# 03_-_CONNECTORS.net
KiCad netlist of a schematic drawn in Altium Designer
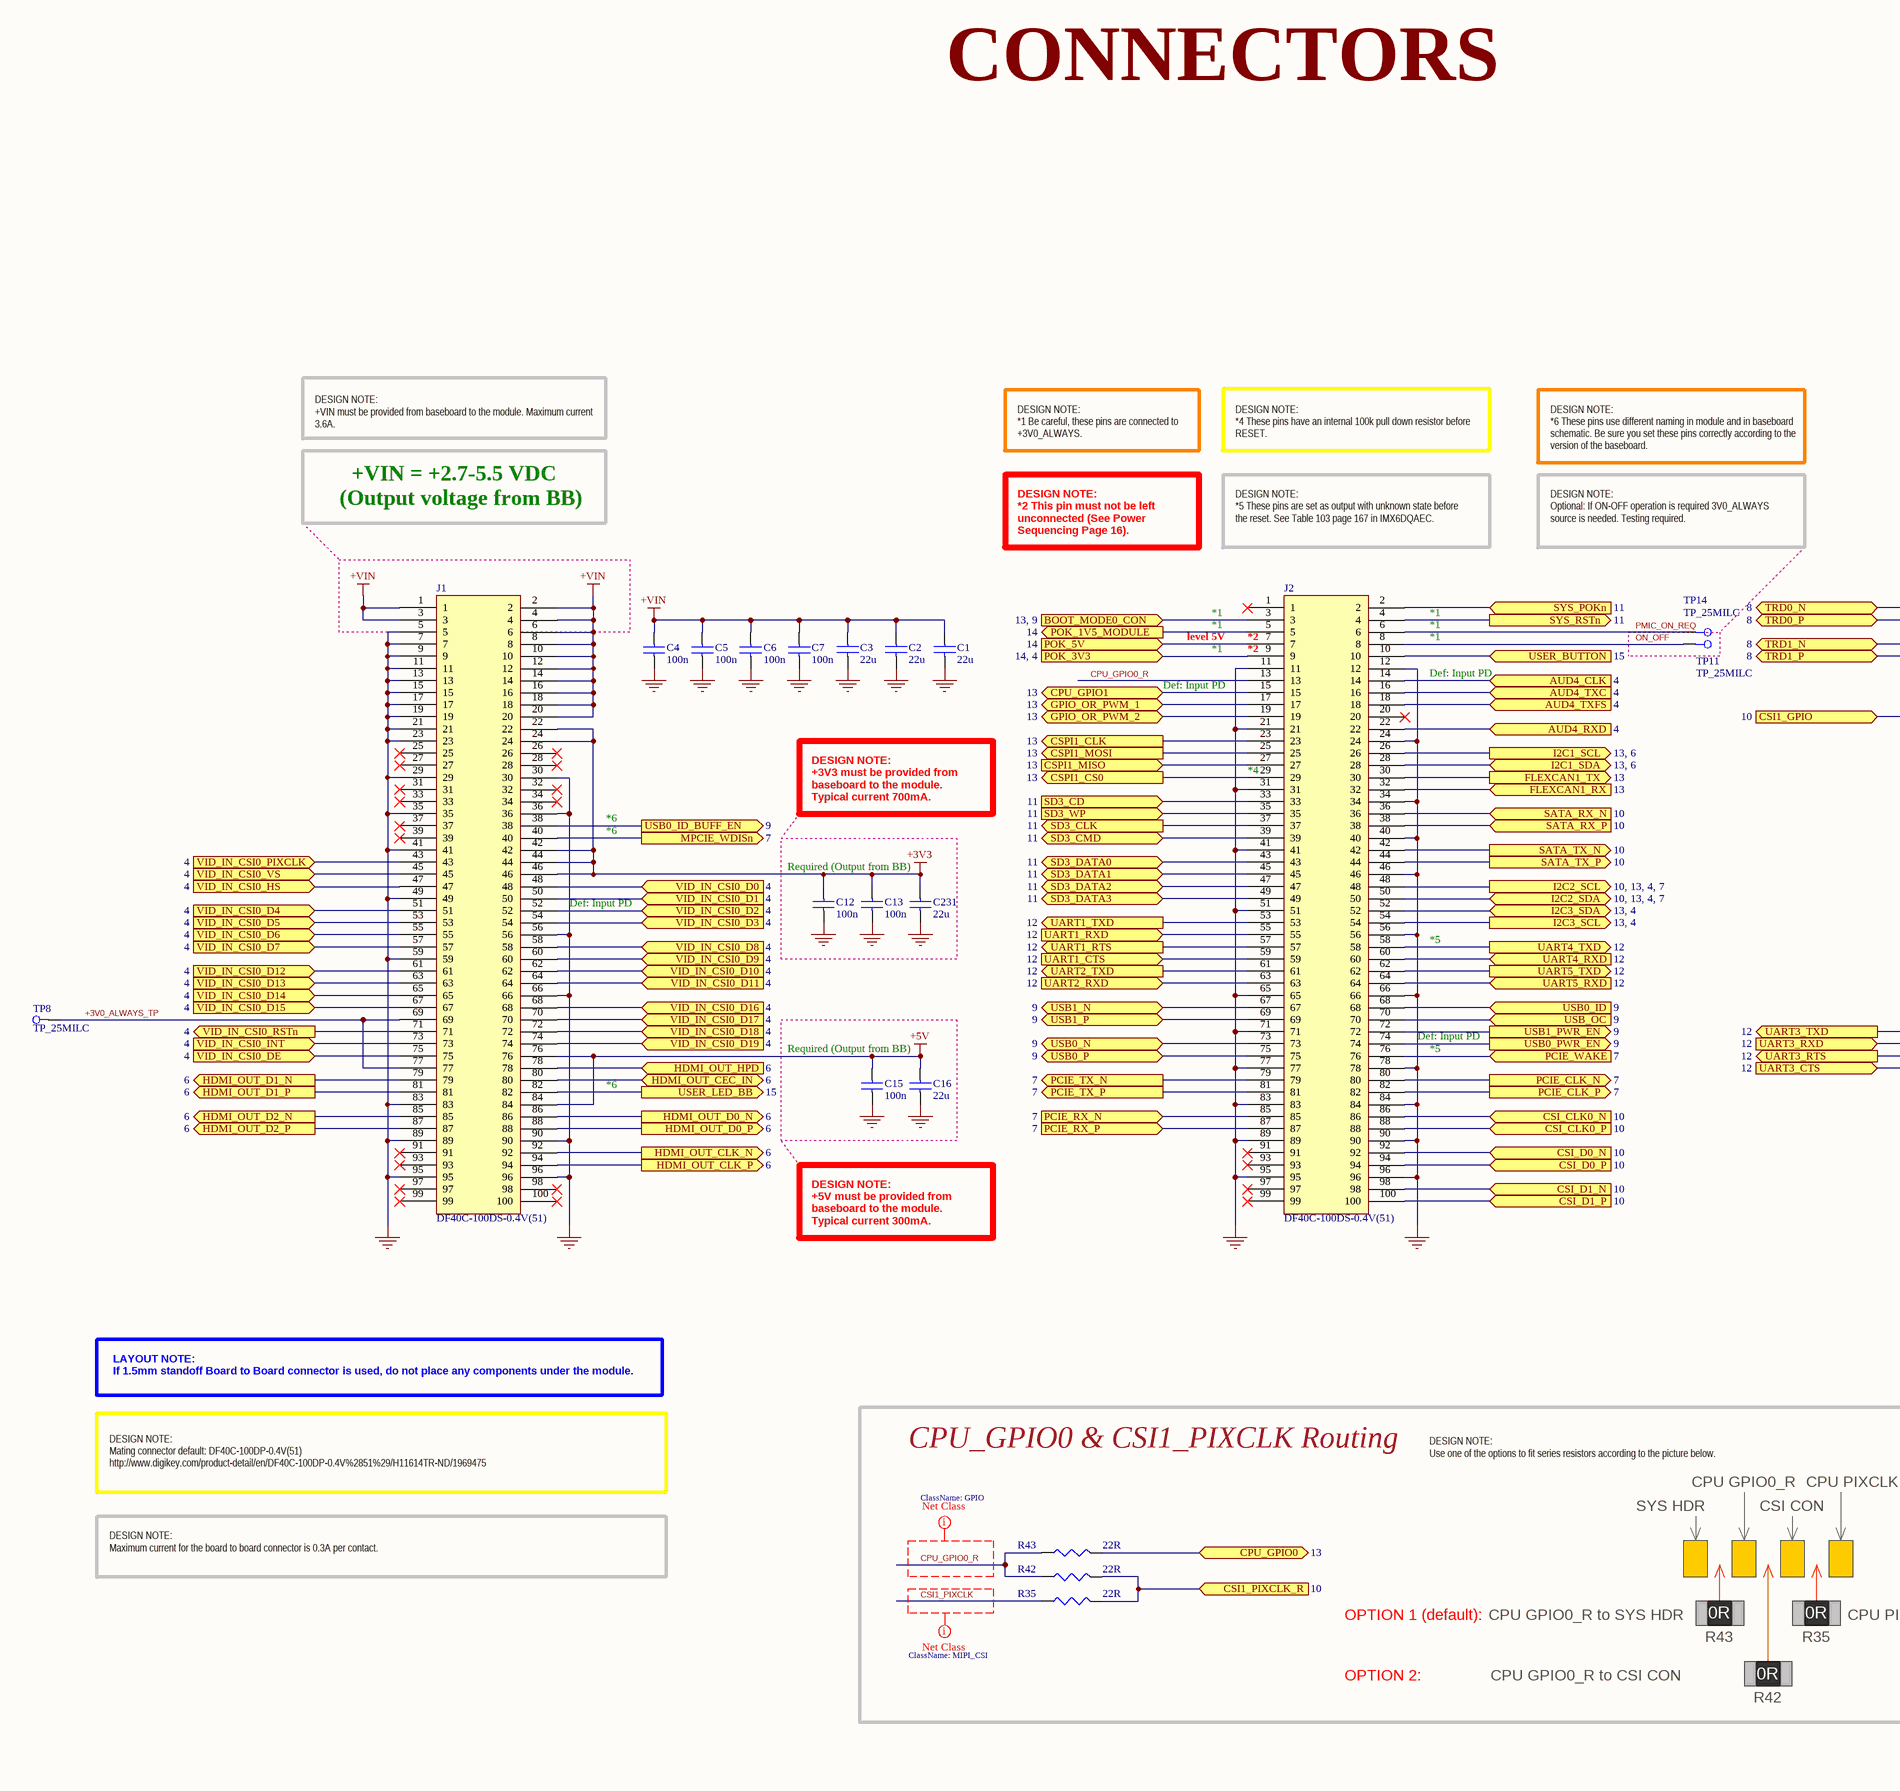
[diagram p0: [03] - CONNECTORS.SchDoc, left]
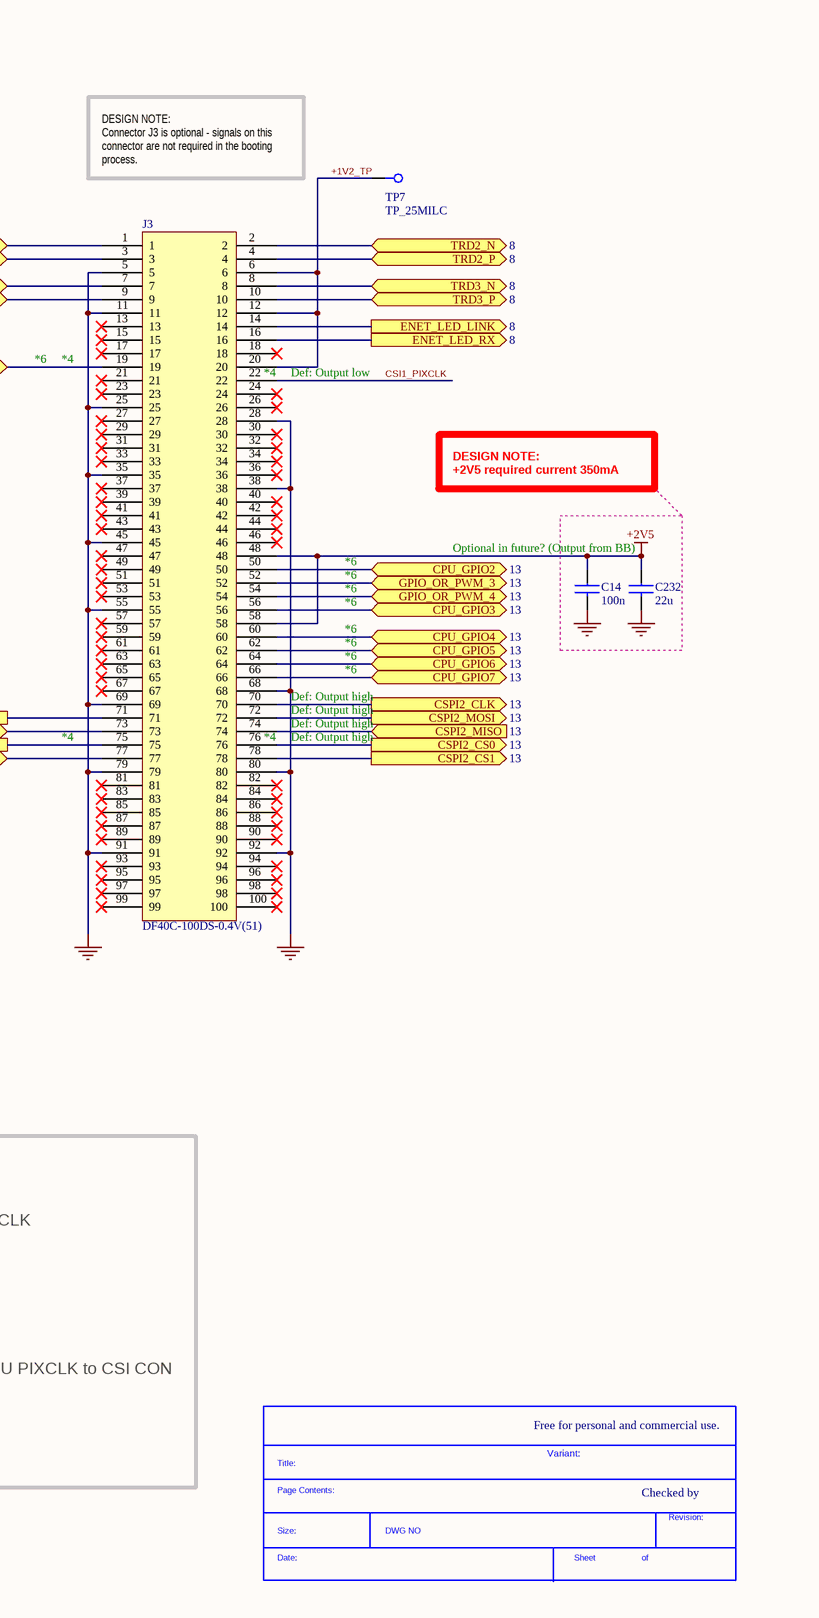
[diagram p1: [03] - CONNECTORS.SchDoc, right]

(export (version "E")
  (design (tool "Eeschema 10.0.6"))
  (components
    (comp (ref "C1")
      (value "22u")
      (footprint "C0603")
      (description "CAP CER 22UF 6.3V 20% X5R 0603")
      (fields
        (field (name "MANUFACTURER") "TDK Corporation")
        (field (name "MANUFACTURER PART NUMBER") "C1608X5R0J226M080AC")
        (field (name ".CREATOR") "MM")
        (field (name ".CHECKED PCB") "MM")
        (field (name ".CHECKED SCH") "MM")
      )
      (libsource (lib "Integrated_Library_FEDEVEL_APR_2015") (part "C1608X5R0J226M080AC"))
    )
    (comp (ref "C2")
      (value "22u")
      (footprint "C0603")
      (description "CAP CER 22UF 6.3V 20% X5R 0603")
      (fields
        (field (name "MANUFACTURER") "TDK Corporation")
        (field (name "MANUFACTURER PART NUMBER") "C1608X5R0J226M080AC")
        (field (name ".CREATOR") "MM")
        (field (name ".CHECKED PCB") "MM")
        (field (name ".CHECKED SCH") "MM")
      )
      (libsource (lib "Integrated_Library_FEDEVEL_APR_2015") (part "C1608X5R0J226M080AC"))
    )
    (comp (ref "C3")
      (value "22u")
      (footprint "C0603")
      (description "CAP CER 22UF 6.3V 20% X5R 0603")
      (fields
        (field (name "MANUFACTURER") "TDK Corporation")
        (field (name "MANUFACTURER PART NUMBER") "C1608X5R0J226M080AC")
        (field (name ".CREATOR") "MM")
        (field (name ".CHECKED PCB") "MM")
        (field (name ".CHECKED SCH") "MM")
      )
      (libsource (lib "Integrated_Library_FEDEVEL_APR_2015") (part "C1608X5R0J226M080AC"))
    )
    (comp (ref "C4")
      (value "100n")
      (footprint "C0402")
      (description "CAP CER .10UF 50V X5R 10% 0402")
      (fields
        (field (name "MANUFACTURER") "TDK Corporation")
        (field (name "MANUFACTURER PART NUMBER") "C1005X5R1H104K")
      )
      (libsource (lib "Integrated_Library_FEDEVEL_APR_2015") (part "C1005X5R1H104K"))
    )
    (comp (ref "C5")
      (value "100n")
      (footprint "C0402")
      (description "CAP CER .10UF 50V X5R 10% 0402")
      (fields
        (field (name "MANUFACTURER") "TDK Corporation")
        (field (name "MANUFACTURER PART NUMBER") "C1005X5R1H104K")
      )
      (libsource (lib "Integrated_Library_FEDEVEL_APR_2015") (part "C1005X5R1H104K"))
    )
    (comp (ref "C6")
      (value "100n")
      (footprint "C0402")
      (description "CAP CER .10UF 50V X5R 10% 0402")
      (fields
        (field (name "MANUFACTURER") "TDK Corporation")
        (field (name "MANUFACTURER PART NUMBER") "C1005X5R1H104K")
      )
      (libsource (lib "Integrated_Library_FEDEVEL_APR_2015") (part "C1005X5R1H104K"))
    )
    (comp (ref "C7")
      (value "100n")
      (footprint "C0402")
      (description "CAP CER .10UF 50V X5R 10% 0402")
      (fields
        (field (name "MANUFACTURER") "TDK Corporation")
        (field (name "MANUFACTURER PART NUMBER") "C1005X5R1H104K")
      )
      (libsource (lib "Integrated_Library_FEDEVEL_APR_2015") (part "C1005X5R1H104K"))
    )
    (comp (ref "C12")
      (value "100n")
      (footprint "C0402")
      (description "CAP CER .10UF 50V X5R 10% 0402")
      (fields
        (field (name "MANUFACTURER") "TDK Corporation")
        (field (name "MANUFACTURER PART NUMBER") "C1005X5R1H104K")
      )
      (libsource (lib "Integrated_Library_FEDEVEL_APR_2015") (part "C1005X5R1H104K"))
    )
    (comp (ref "C13")
      (value "100n")
      (footprint "C0402")
      (description "CAP CER .10UF 50V X5R 10% 0402")
      (fields
        (field (name "MANUFACTURER") "TDK Corporation")
        (field (name "MANUFACTURER PART NUMBER") "C1005X5R1H104K")
      )
      (libsource (lib "Integrated_Library_FEDEVEL_APR_2015") (part "C1005X5R1H104K"))
    )
    (comp (ref "C14")
      (value "100n")
      (footprint "C0402")
      (description "CAP CER .10UF 50V X5R 10% 0402")
      (fields
        (field (name "MANUFACTURER") "TDK Corporation")
        (field (name "MANUFACTURER PART NUMBER") "C1005X5R1H104K")
      )
      (libsource (lib "Integrated_Library_FEDEVEL_APR_2015") (part "C1005X5R1H104K"))
    )
    (comp (ref "C15")
      (value "100n")
      (footprint "C0402")
      (description "CAP CER .10UF 50V X5R 10% 0402")
      (fields
        (field (name "MANUFACTURER") "TDK Corporation")
        (field (name "MANUFACTURER PART NUMBER") "C1005X5R1H104K")
      )
      (libsource (lib "Integrated_Library_FEDEVEL_APR_2015") (part "C1005X5R1H104K"))
    )
    (comp (ref "C16")
      (value "22u")
      (footprint "C0603")
      (description "CAP CER 22UF 6.3V 20% X5R 0603")
      (fields
        (field (name "MANUFACTURER") "TDK Corporation")
        (field (name "MANUFACTURER PART NUMBER") "C1608X5R0J226M080AC")
        (field (name ".CREATOR") "MM")
        (field (name ".CHECKED PCB") "MM")
        (field (name ".CHECKED SCH") "MM")
      )
      (libsource (lib "Integrated_Library_FEDEVEL_APR_2015") (part "C1608X5R0J226M080AC"))
    )
    (comp (ref "C231")
      (value "22u")
      (footprint "C0603")
      (description "CAP CER 22UF 6.3V 20% X5R 0603")
      (fields
        (field (name "MANUFACTURER") "TDK Corporation")
        (field (name "MANUFACTURER PART NUMBER") "C1608X5R0J226M080AC")
        (field (name ".CREATOR") "MM")
        (field (name ".CHECKED PCB") "MM")
        (field (name ".CHECKED SCH") "MM")
      )
      (libsource (lib "Integrated_Library_FEDEVEL_APR_2015") (part "C1608X5R0J226M080AC"))
    )
    (comp (ref "C232")
      (value "22u")
      (footprint "C0603")
      (description "CAP CER 22UF 6.3V 20% X5R 0603")
      (fields
        (field (name "MANUFACTURER") "TDK Corporation")
        (field (name "MANUFACTURER PART NUMBER") "C1608X5R0J226M080AC")
        (field (name ".CREATOR") "MM")
        (field (name ".CHECKED PCB") "MM")
        (field (name ".CHECKED SCH") "MM")
      )
      (libsource (lib "Integrated_Library_FEDEVEL_APR_2015") (part "C1608X5R0J226M080AC"))
    )
    (comp (ref "J1")
      (value "DF40C-100DS-0.4V(51)")
      (footprint "DF40C-100DS-0.4V(51)_V1.1")
      (description "CONN RCPT 100POS 0.4MM SMD GOLD")
      (fields
        (field (name "MANUFACTURER") "Hirose Electric Co Ltd")
        (field (name ".CREATOR") "MM")
        (field (name ".CHECKED PCB") "MM")
        (field (name ".CHECKED SCH") "MM")
      )
      (libsource (lib "Integrated_Library_FEDEVEL_APR_2015") (part "DF40C-100DS-0.4V(51)_v1.1"))
    )
    (comp (ref "J2")
      (value "DF40C-100DS-0.4V(51)")
      (footprint "DF40C-100DS-0.4V(51)_V1.1")
      (description "CONN RCPT 100POS 0.4MM SMD GOLD")
      (fields
        (field (name "MANUFACTURER") "Hirose Electric Co Ltd")
        (field (name ".CREATOR") "MM")
        (field (name ".CHECKED PCB") "MM")
        (field (name ".CHECKED SCH") "MM")
      )
      (libsource (lib "Integrated_Library_FEDEVEL_APR_2015") (part "DF40C-100DS-0.4V(51)_v1.1"))
    )
    (comp (ref "J3")
      (value "DF40C-100DS-0.4V(51)")
      (footprint "DF40C-100DS-0.4V(51)_V1.1")
      (description "CONN RCPT 100POS 0.4MM SMD GOLD")
      (fields
        (field (name "MANUFACTURER") "Hirose Electric Co Ltd")
        (field (name ".CREATOR") "MM")
        (field (name ".CHECKED PCB") "MM")
        (field (name ".CHECKED SCH") "MM")
      )
      (libsource (lib "Integrated_Library_FEDEVEL_APR_2015") (part "DF40C-100DS-0.4V(51)_v1.1"))
    )
    (comp (ref "R35")
      (value "22R")
      (footprint "R0402")
      (description "RES 22.0 OHM 1/16W 1% 0402 SMD")
      (fields
        (field (name "MANUFACTURER") "Yageo")
        (field (name "MANUFACTURER PART NUMBER") "RC0402FR-0722RL")
      )
      (libsource (lib "Integrated_Library_FEDEVEL_APR_2015") (part "RC0402FR-0722RL"))
    )
    (comp (ref "R42")
      (value "22R")
      (footprint "R0402")
      (description "RES 22.0 OHM 1/16W 1% 0402 SMD")
      (fields
        (field (name "MANUFACTURER") "Yageo")
        (field (name "MANUFACTURER PART NUMBER") "RC0402FR-0722RL")
      )
      (libsource (lib "Integrated_Library_FEDEVEL_APR_2015") (part "RC0402FR-0722RL"))
    )
    (comp (ref "R43")
      (value "22R")
      (footprint "R0402")
      (description "RES 22.0 OHM 1/16W 1% 0402 SMD")
      (fields
        (field (name "MANUFACTURER") "Yageo")
        (field (name "MANUFACTURER PART NUMBER") "RC0402FR-0722RL")
      )
      (libsource (lib "Integrated_Library_FEDEVEL_APR_2015") (part "RC0402FR-0722RL"))
    )
    (comp (ref "TP7")
      (value "TP_25MILC")
      (footprint "TP_25C")
      (description "Test Point 25mil")
      (libsource (lib "Integrated_Library_FEDEVEL_APR_2015") (part "TP_25MILC"))
    )
    (comp (ref "TP8")
      (value "TP_25MILC")
      (footprint "TP_25C")
      (description "Test Point 25mil")
      (libsource (lib "Integrated_Library_FEDEVEL_APR_2015") (part "TP_25MILC"))
    )
    (comp (ref "TP11")
      (value "TP_25MILC")
      (footprint "TP_25C")
      (description "Test Point 25mil")
      (libsource (lib "Integrated_Library_FEDEVEL_APR_2015") (part "TP_25MILC"))
    )
    (comp (ref "TP14")
      (value "TP_25MILC")
      (footprint "TP_25C")
      (description "Test Point 25mil")
      (libsource (lib "Integrated_Library_FEDEVEL_APR_2015") (part "TP_25MILC"))
    )
  )
  (nets
    (net (code "1") (name "+2V5") (class "Default")
      (node (ref "C14") (pin "1") (pinfunction "1_1") (pintype "passive"))
      (node (ref "C232") (pin "1") (pinfunction "1_1") (pintype "passive"))
      (node (ref "J3") (pin "48") (pinfunction "48_48") (pintype "passive"))
      (node (ref "J3") (pin "58") (pinfunction "58_58") (pintype "passive"))
    )
    (net (code "2") (name "+3V3") (class "Default")
      (node (ref "C12") (pin "1") (pinfunction "1_1") (pintype "passive"))
      (node (ref "C13") (pin "1") (pinfunction "1_1") (pintype "passive"))
      (node (ref "C231") (pin "1") (pinfunction "1_1") (pintype "passive"))
      (node (ref "J1") (pin "22") (pinfunction "22_22") (pintype "passive"))
      (node (ref "J1") (pin "24") (pinfunction "24_24") (pintype "passive"))
      (node (ref "J1") (pin "42") (pinfunction "42_42") (pintype "passive"))
      (node (ref "J1") (pin "44") (pinfunction "44_44") (pintype "passive"))
      (node (ref "J1") (pin "46") (pinfunction "46_46") (pintype "passive"))
    )
    (net (code "3") (name "+5V") (class "Default")
      (node (ref "C15") (pin "1") (pinfunction "1_1") (pintype "passive"))
      (node (ref "C16") (pin "1") (pinfunction "1_1") (pintype "passive"))
      (node (ref "J1") (pin "76") (pinfunction "76_76") (pintype "passive"))
      (node (ref "J1") (pin "84") (pinfunction "84_84") (pintype "passive"))
    )
    (net (code "4") (name "+VIN") (class "Default")
      (node (ref "C1") (pin "1") (pinfunction "1_1") (pintype "passive"))
      (node (ref "C2") (pin "1") (pinfunction "1_1") (pintype "passive"))
      (node (ref "C3") (pin "1") (pinfunction "1_1") (pintype "passive"))
      (node (ref "C4") (pin "1") (pinfunction "1_1") (pintype "passive"))
      (node (ref "C5") (pin "1") (pinfunction "1_1") (pintype "passive"))
      (node (ref "C6") (pin "1") (pinfunction "1_1") (pintype "passive"))
      (node (ref "C7") (pin "1") (pinfunction "1_1") (pintype "passive"))
      (node (ref "J1") (pin "1") (pinfunction "1_1") (pintype "passive"))
      (node (ref "J1") (pin "10") (pinfunction "10_10") (pintype "passive"))
      (node (ref "J1") (pin "12") (pinfunction "12_12") (pintype "passive"))
      (node (ref "J1") (pin "14") (pinfunction "14_14") (pintype "passive"))
      (node (ref "J1") (pin "16") (pinfunction "16_16") (pintype "passive"))
      (node (ref "J1") (pin "18") (pinfunction "18_18") (pintype "passive"))
      (node (ref "J1") (pin "2") (pinfunction "2_2") (pintype "passive"))
      (node (ref "J1") (pin "20") (pinfunction "20_20") (pintype "passive"))
      (node (ref "J1") (pin "3") (pinfunction "3_3") (pintype "passive"))
      (node (ref "J1") (pin "4") (pinfunction "4_4") (pintype "passive"))
      (node (ref "J1") (pin "6") (pinfunction "6_6") (pintype "passive"))
      (node (ref "J1") (pin "8") (pinfunction "8_8") (pintype "passive"))
    )
    (net (code "5") (name "/+1V2_TP") (class "Default")
      (node (ref "J3") (pin "12") (pinfunction "12_12") (pintype "passive"))
      (node (ref "J3") (pin "20") (pinfunction "20_20") (pintype "passive"))
      (node (ref "J3") (pin "6") (pinfunction "6_6") (pintype "passive"))
      (node (ref "TP7") (pin "1") (pinfunction "1_1") (pintype "passive"))
    )
    (net (code "6") (name "/+3V0_ALWAYS_TP") (class "Default")
      (node (ref "J1") (pin "69") (pinfunction "69_69") (pintype "passive"))
      (node (ref "J1") (pin "77") (pinfunction "77_77") (pintype "passive"))
      (node (ref "TP8") (pin "1") (pinfunction "1_1") (pintype "passive"))
    )
    (net (code "7") (name "/AUD4_CLK") (class "Default")
      (node (ref "J2") (pin "14") (pinfunction "14_14") (pintype "passive"))
    )
    (net (code "8") (name "/AUD4_RXD") (class "Default")
      (node (ref "J2") (pin "22") (pinfunction "22_22") (pintype "passive"))
    )
    (net (code "9") (name "/AUD4_TXC") (class "Default")
      (node (ref "J2") (pin "16") (pinfunction "16_16") (pintype "passive"))
    )
    (net (code "10") (name "/AUD4_TXFS") (class "Default")
      (node (ref "J2") (pin "18") (pinfunction "18_18") (pintype "passive"))
    )
    (net (code "11") (name "/BOOT_MODE0_CON") (class "Default")
      (node (ref "J2") (pin "3") (pinfunction "3_3") (pintype "passive"))
    )
    (net (code "12") (name "/CPU_GPIO0") (class "Default")
      (node (ref "R43") (pin "2") (pinfunction "2_2") (pintype "passive"))
    )
    (net (code "13") (name "/CPU_GPIO0_R") (class "Default")
      (node (ref "J2") (pin "13") (pinfunction "13_13") (pintype "passive"))
      (node (ref "R42") (pin "1") (pinfunction "1_1") (pintype "passive"))
      (node (ref "R43") (pin "1") (pinfunction "1_1") (pintype "passive"))
    )
    (net (code "14") (name "/CPU_GPIO1") (class "Default")
      (node (ref "J2") (pin "15") (pinfunction "15_15") (pintype "passive"))
    )
    (net (code "15") (name "/CPU_GPIO2") (class "Default")
      (node (ref "J3") (pin "50") (pinfunction "50_50") (pintype "passive"))
    )
    (net (code "16") (name "/CPU_GPIO3") (class "Default")
      (node (ref "J3") (pin "56") (pinfunction "56_56") (pintype "passive"))
    )
    (net (code "17") (name "/CPU_GPIO4") (class "Default")
      (node (ref "J3") (pin "60") (pinfunction "60_60") (pintype "passive"))
    )
    (net (code "18") (name "/CPU_GPIO5") (class "Default")
      (node (ref "J3") (pin "62") (pinfunction "62_62") (pintype "passive"))
    )
    (net (code "19") (name "/CPU_GPIO6") (class "Default")
      (node (ref "J3") (pin "64") (pinfunction "64_64") (pintype "passive"))
    )
    (net (code "20") (name "/CPU_GPIO7") (class "Default")
      (node (ref "J3") (pin "66") (pinfunction "66_66") (pintype "passive"))
    )
    (net (code "21") (name "/CSI1_GPIO") (class "Default")
      (node (ref "J3") (pin "19") (pinfunction "19_19") (pintype "passive"))
    )
    (net (code "22") (name "/CSI1_PIXCLK") (class "Default")
      (node (ref "J3") (pin "22") (pinfunction "22_22") (pintype "passive"))
      (node (ref "R35") (pin "1") (pinfunction "1_1") (pintype "passive"))
    )
    (net (code "23") (name "/CSI1_PIXCLK_R") (class "Default")
      (node (ref "R35") (pin "2") (pinfunction "2_2") (pintype "passive"))
      (node (ref "R42") (pin "2") (pinfunction "2_2") (pintype "passive"))
    )
    (net (code "24") (name "/CSI_CLK0_N") (class "Default")
      (node (ref "J2") (pin "86") (pinfunction "86_86") (pintype "passive"))
    )
    (net (code "25") (name "/CSI_CLK0_P") (class "Default")
      (node (ref "J2") (pin "88") (pinfunction "88_88") (pintype "passive"))
    )
    (net (code "26") (name "/CSI_D0_N") (class "Default")
      (node (ref "J2") (pin "92") (pinfunction "92_92") (pintype "passive"))
    )
    (net (code "27") (name "/CSI_D0_P") (class "Default")
      (node (ref "J2") (pin "94") (pinfunction "94_94") (pintype "passive"))
    )
    (net (code "28") (name "/CSI_D1_N") (class "Default")
      (node (ref "J2") (pin "98") (pinfunction "98_98") (pintype "passive"))
    )
    (net (code "29") (name "/CSI_D1_P") (class "Default")
      (node (ref "J2") (pin "100") (pinfunction "100_100") (pintype "passive"))
    )
    (net (code "30") (name "/CSPI1_CLK") (class "Default")
      (node (ref "J2") (pin "23") (pinfunction "23_23") (pintype "passive"))
    )
    (net (code "31") (name "/CSPI1_CS0") (class "Default")
      (node (ref "J2") (pin "29") (pinfunction "29_29") (pintype "passive"))
    )
    (net (code "32") (name "/CSPI1_MISO") (class "Default")
      (node (ref "J2") (pin "27") (pinfunction "27_27") (pintype "passive"))
    )
    (net (code "33") (name "/CSPI1_MOSI") (class "Default")
      (node (ref "J2") (pin "25") (pinfunction "25_25") (pintype "passive"))
    )
    (net (code "34") (name "/CSPI2_CLK") (class "Default")
      (node (ref "J3") (pin "70") (pinfunction "70_70") (pintype "passive"))
    )
    (net (code "35") (name "/CSPI2_CS0") (class "Default")
      (node (ref "J3") (pin "76") (pinfunction "76_76") (pintype "passive"))
    )
    (net (code "36") (name "/CSPI2_CS1") (class "Default")
      (node (ref "J3") (pin "78") (pinfunction "78_78") (pintype "passive"))
    )
    (net (code "37") (name "/CSPI2_MISO") (class "Default")
      (node (ref "J3") (pin "74") (pinfunction "74_74") (pintype "passive"))
    )
    (net (code "38") (name "/CSPI2_MOSI") (class "Default")
      (node (ref "J3") (pin "72") (pinfunction "72_72") (pintype "passive"))
    )
    (net (code "39") (name "/ENET_LED_LINK") (class "Default")
      (node (ref "J3") (pin "14") (pinfunction "14_14") (pintype "passive"))
    )
    (net (code "40") (name "/ENET_LED_RX") (class "Default")
      (node (ref "J3") (pin "16") (pinfunction "16_16") (pintype "passive"))
    )
    (net (code "41") (name "/FLEXCAN1_RX") (class "Default")
      (node (ref "J2") (pin "32") (pinfunction "32_32") (pintype "passive"))
    )
    (net (code "42") (name "/FLEXCAN1_TX") (class "Default")
      (node (ref "J2") (pin "30") (pinfunction "30_30") (pintype "passive"))
    )
    (net (code "43") (name "/GPIO_OR_PWM_1") (class "Default")
      (node (ref "J2") (pin "17") (pinfunction "17_17") (pintype "passive"))
    )
    (net (code "44") (name "/GPIO_OR_PWM_2") (class "Default")
      (node (ref "J2") (pin "19") (pinfunction "19_19") (pintype "passive"))
    )
    (net (code "45") (name "/GPIO_OR_PWM_3") (class "Default")
      (node (ref "J3") (pin "52") (pinfunction "52_52") (pintype "passive"))
    )
    (net (code "46") (name "/GPIO_OR_PWM_4") (class "Default")
      (node (ref "J3") (pin "54") (pinfunction "54_54") (pintype "passive"))
    )
    (net (code "47") (name "/HDMI_OUT_CEC_IN") (class "Default")
      (node (ref "J1") (pin "80") (pinfunction "80_80") (pintype "passive"))
    )
    (net (code "48") (name "/HDMI_OUT_CLK_N") (class "Default")
      (node (ref "J1") (pin "92") (pinfunction "92_92") (pintype "passive"))
    )
    (net (code "49") (name "/HDMI_OUT_CLK_P") (class "Default")
      (node (ref "J1") (pin "94") (pinfunction "94_94") (pintype "passive"))
    )
    (net (code "50") (name "/HDMI_OUT_D0_N") (class "Default")
      (node (ref "J1") (pin "86") (pinfunction "86_86") (pintype "passive"))
    )
    (net (code "51") (name "/HDMI_OUT_D0_P") (class "Default")
      (node (ref "J1") (pin "88") (pinfunction "88_88") (pintype "passive"))
    )
    (net (code "52") (name "/HDMI_OUT_D1_N") (class "Default")
      (node (ref "J1") (pin "79") (pinfunction "79_79") (pintype "passive"))
    )
    (net (code "53") (name "/HDMI_OUT_D1_P") (class "Default")
      (node (ref "J1") (pin "81") (pinfunction "81_81") (pintype "passive"))
    )
    (net (code "54") (name "/HDMI_OUT_D2_N") (class "Default")
      (node (ref "J1") (pin "85") (pinfunction "85_85") (pintype "passive"))
    )
    (net (code "55") (name "/HDMI_OUT_D2_P") (class "Default")
      (node (ref "J1") (pin "87") (pinfunction "87_87") (pintype "passive"))
    )
    (net (code "56") (name "/HDMI_OUT_HPD") (class "Default")
      (node (ref "J1") (pin "78") (pinfunction "78_78") (pintype "passive"))
    )
    (net (code "57") (name "/I2C1_SCL") (class "Default")
      (node (ref "J2") (pin "26") (pinfunction "26_26") (pintype "passive"))
    )
    (net (code "58") (name "/I2C1_SDA") (class "Default")
      (node (ref "J2") (pin "28") (pinfunction "28_28") (pintype "passive"))
    )
    (net (code "59") (name "/I2C2_SCL") (class "Default")
      (node (ref "J2") (pin "48") (pinfunction "48_48") (pintype "passive"))
    )
    (net (code "60") (name "/I2C2_SDA") (class "Default")
      (node (ref "J2") (pin "50") (pinfunction "50_50") (pintype "passive"))
    )
    (net (code "61") (name "/I2C3_SCL") (class "Default")
      (node (ref "J2") (pin "54") (pinfunction "54_54") (pintype "passive"))
    )
    (net (code "62") (name "/I2C3_SDA") (class "Default")
      (node (ref "J2") (pin "52") (pinfunction "52_52") (pintype "passive"))
    )
    (net (code "63") (name "/MPCIE_WDISn") (class "Default")
      (node (ref "J1") (pin "40") (pinfunction "40_40") (pintype "passive"))
    )
    (net (code "64") (name "/ON_OFF") (class "Default")
      (node (ref "J2") (pin "8") (pinfunction "8_8") (pintype "passive"))
      (node (ref "TP11") (pin "1") (pinfunction "1_1") (pintype "passive"))
    )
    (net (code "65") (name "/PCIE_CLK_N") (class "Default")
      (node (ref "J2") (pin "80") (pinfunction "80_80") (pintype "passive"))
    )
    (net (code "66") (name "/PCIE_CLK_P") (class "Default")
      (node (ref "J2") (pin "82") (pinfunction "82_82") (pintype "passive"))
    )
    (net (code "67") (name "/PCIE_RX_N") (class "Default")
      (node (ref "J2") (pin "85") (pinfunction "85_85") (pintype "passive"))
    )
    (net (code "68") (name "/PCIE_RX_P") (class "Default")
      (node (ref "J2") (pin "87") (pinfunction "87_87") (pintype "passive"))
    )
    (net (code "69") (name "/PCIE_TX_N") (class "Default")
      (node (ref "J2") (pin "79") (pinfunction "79_79") (pintype "passive"))
    )
    (net (code "70") (name "/PCIE_TX_P") (class "Default")
      (node (ref "J2") (pin "81") (pinfunction "81_81") (pintype "passive"))
    )
    (net (code "71") (name "/PCIE_WAKE") (class "Default")
      (node (ref "J2") (pin "76") (pinfunction "76_76") (pintype "passive"))
    )
    (net (code "72") (name "/PMIC_ON_REQ") (class "Default")
      (node (ref "J2") (pin "6") (pinfunction "6_6") (pintype "passive"))
      (node (ref "TP14") (pin "1") (pinfunction "1_1") (pintype "passive"))
    )
    (net (code "73") (name "/POK_1V5_MODULE") (class "Default")
      (node (ref "J2") (pin "5") (pinfunction "5_5") (pintype "passive"))
    )
    (net (code "74") (name "/POK_3V3") (class "Default")
      (node (ref "J2") (pin "9") (pinfunction "9_9") (pintype "passive"))
    )
    (net (code "75") (name "/POK_5V") (class "Default")
      (node (ref "J2") (pin "7") (pinfunction "7_7") (pintype "passive"))
    )
    (net (code "76") (name "/SATA_RX_N") (class "Default")
      (node (ref "J2") (pin "36") (pinfunction "36_36") (pintype "passive"))
    )
    (net (code "77") (name "/SATA_RX_P") (class "Default")
      (node (ref "J2") (pin "38") (pinfunction "38_38") (pintype "passive"))
    )
    (net (code "78") (name "/SATA_TX_N") (class "Default")
      (node (ref "J2") (pin "42") (pinfunction "42_42") (pintype "passive"))
    )
    (net (code "79") (name "/SATA_TX_P") (class "Default")
      (node (ref "J2") (pin "44") (pinfunction "44_44") (pintype "passive"))
    )
    (net (code "80") (name "/SD3_CD") (class "Default")
      (node (ref "J2") (pin "33") (pinfunction "33_33") (pintype "passive"))
    )
    (net (code "81") (name "/SD3_CLK") (class "Default")
      (node (ref "J2") (pin "37") (pinfunction "37_37") (pintype "passive"))
    )
    (net (code "82") (name "/SD3_CMD") (class "Default")
      (node (ref "J2") (pin "39") (pinfunction "39_39") (pintype "passive"))
    )
    (net (code "83") (name "/SD3_DATA0") (class "Default")
      (node (ref "J2") (pin "43") (pinfunction "43_43") (pintype "passive"))
    )
    (net (code "84") (name "/SD3_DATA1") (class "Default")
      (node (ref "J2") (pin "45") (pinfunction "45_45") (pintype "passive"))
    )
    (net (code "85") (name "/SD3_DATA2") (class "Default")
      (node (ref "J2") (pin "47") (pinfunction "47_47") (pintype "passive"))
    )
    (net (code "86") (name "/SD3_DATA3") (class "Default")
      (node (ref "J2") (pin "49") (pinfunction "49_49") (pintype "passive"))
    )
    (net (code "87") (name "/SD3_WP") (class "Default")
      (node (ref "J2") (pin "35") (pinfunction "35_35") (pintype "passive"))
    )
    (net (code "88") (name "/SYS_POKn") (class "Default")
      (node (ref "J2") (pin "2") (pinfunction "2_2") (pintype "passive"))
    )
    (net (code "89") (name "/SYS_RSTn") (class "Default")
      (node (ref "J2") (pin "4") (pinfunction "4_4") (pintype "passive"))
    )
    (net (code "90") (name "/TRD0_N") (class "Default")
      (node (ref "J3") (pin "1") (pinfunction "1_1") (pintype "passive"))
    )
    (net (code "91") (name "/TRD0_P") (class "Default")
      (node (ref "J3") (pin "3") (pinfunction "3_3") (pintype "passive"))
    )
    (net (code "92") (name "/TRD1_N") (class "Default")
      (node (ref "J3") (pin "7") (pinfunction "7_7") (pintype "passive"))
    )
    (net (code "93") (name "/TRD1_P") (class "Default")
      (node (ref "J3") (pin "9") (pinfunction "9_9") (pintype "passive"))
    )
    (net (code "94") (name "/TRD2_N") (class "Default")
      (node (ref "J3") (pin "2") (pinfunction "2_2") (pintype "passive"))
    )
    (net (code "95") (name "/TRD2_P") (class "Default")
      (node (ref "J3") (pin "4") (pinfunction "4_4") (pintype "passive"))
    )
    (net (code "96") (name "/TRD3_N") (class "Default")
      (node (ref "J3") (pin "8") (pinfunction "8_8") (pintype "passive"))
    )
    (net (code "97") (name "/TRD3_P") (class "Default")
      (node (ref "J3") (pin "10") (pinfunction "10_10") (pintype "passive"))
    )
    (net (code "98") (name "/UART1_CTS") (class "Default")
      (node (ref "J2") (pin "59") (pinfunction "59_59") (pintype "passive"))
    )
    (net (code "99") (name "/UART1_RTS") (class "Default")
      (node (ref "J2") (pin "57") (pinfunction "57_57") (pintype "passive"))
    )
    (net (code "100") (name "/UART1_RXD") (class "Default")
      (node (ref "J2") (pin "55") (pinfunction "55_55") (pintype "passive"))
    )
    (net (code "101") (name "/UART1_TXD") (class "Default")
      (node (ref "J2") (pin "53") (pinfunction "53_53") (pintype "passive"))
    )
    (net (code "102") (name "/UART2_RXD") (class "Default")
      (node (ref "J2") (pin "63") (pinfunction "63_63") (pintype "passive"))
    )
    (net (code "103") (name "/UART2_TXD") (class "Default")
      (node (ref "J2") (pin "61") (pinfunction "61_61") (pintype "passive"))
    )
    (net (code "104") (name "/UART3_CTS") (class "Default")
      (node (ref "J3") (pin "77") (pinfunction "77_77") (pintype "passive"))
    )
    (net (code "105") (name "/UART3_RTS") (class "Default")
      (node (ref "J3") (pin "75") (pinfunction "75_75") (pintype "passive"))
    )
    (net (code "106") (name "/UART3_RXD") (class "Default")
      (node (ref "J3") (pin "73") (pinfunction "73_73") (pintype "passive"))
    )
    (net (code "107") (name "/UART3_TXD") (class "Default")
      (node (ref "J3") (pin "71") (pinfunction "71_71") (pintype "passive"))
    )
    (net (code "108") (name "/UART4_RXD") (class "Default")
      (node (ref "J2") (pin "60") (pinfunction "60_60") (pintype "passive"))
    )
    (net (code "109") (name "/UART4_TXD") (class "Default")
      (node (ref "J2") (pin "58") (pinfunction "58_58") (pintype "passive"))
    )
    (net (code "110") (name "/UART5_RXD") (class "Default")
      (node (ref "J2") (pin "64") (pinfunction "64_64") (pintype "passive"))
    )
    (net (code "111") (name "/UART5_TXD") (class "Default")
      (node (ref "J2") (pin "62") (pinfunction "62_62") (pintype "passive"))
    )
    (net (code "112") (name "/USB0_ID") (class "Default")
      (node (ref "J2") (pin "68") (pinfunction "68_68") (pintype "passive"))
    )
    (net (code "113") (name "/USB0_ID_BUFF_EN") (class "Default")
      (node (ref "J1") (pin "38") (pinfunction "38_38") (pintype "passive"))
    )
    (net (code "114") (name "/USB0_N") (class "Default")
      (node (ref "J2") (pin "73") (pinfunction "73_73") (pintype "passive"))
    )
    (net (code "115") (name "/USB0_P") (class "Default")
      (node (ref "J2") (pin "75") (pinfunction "75_75") (pintype "passive"))
    )
    (net (code "116") (name "/USB0_PWR_EN") (class "Default")
      (node (ref "J2") (pin "74") (pinfunction "74_74") (pintype "passive"))
    )
    (net (code "117") (name "/USB1_N") (class "Default")
      (node (ref "J2") (pin "67") (pinfunction "67_67") (pintype "passive"))
    )
    (net (code "118") (name "/USB1_P") (class "Default")
      (node (ref "J2") (pin "69") (pinfunction "69_69") (pintype "passive"))
    )
    (net (code "119") (name "/USB1_PWR_EN") (class "Default")
      (node (ref "J2") (pin "72") (pinfunction "72_72") (pintype "passive"))
    )
    (net (code "120") (name "/USB_OC") (class "Default")
      (node (ref "J2") (pin "70") (pinfunction "70_70") (pintype "passive"))
    )
    (net (code "121") (name "/USER_BUTTON") (class "Default")
      (node (ref "J2") (pin "10") (pinfunction "10_10") (pintype "passive"))
    )
    (net (code "122") (name "/USER_LED_BB") (class "Default")
      (node (ref "J1") (pin "82") (pinfunction "82_82") (pintype "passive"))
    )
    (net (code "123") (name "/VID_IN_CSI0_D0") (class "Default")
      (node (ref "J1") (pin "48") (pinfunction "48_48") (pintype "passive"))
    )
    (net (code "124") (name "/VID_IN_CSI0_D1") (class "Default")
      (node (ref "J1") (pin "50") (pinfunction "50_50") (pintype "passive"))
    )
    (net (code "125") (name "/VID_IN_CSI0_D2") (class "Default")
      (node (ref "J1") (pin "52") (pinfunction "52_52") (pintype "passive"))
    )
    (net (code "126") (name "/VID_IN_CSI0_D3") (class "Default")
      (node (ref "J1") (pin "54") (pinfunction "54_54") (pintype "passive"))
    )
    (net (code "127") (name "/VID_IN_CSI0_D4") (class "Default")
      (node (ref "J1") (pin "51") (pinfunction "51_51") (pintype "passive"))
    )
    (net (code "128") (name "/VID_IN_CSI0_D5") (class "Default")
      (node (ref "J1") (pin "53") (pinfunction "53_53") (pintype "passive"))
    )
    (net (code "129") (name "/VID_IN_CSI0_D6") (class "Default")
      (node (ref "J1") (pin "55") (pinfunction "55_55") (pintype "passive"))
    )
    (net (code "130") (name "/VID_IN_CSI0_D7") (class "Default")
      (node (ref "J1") (pin "57") (pinfunction "57_57") (pintype "passive"))
    )
    (net (code "131") (name "/VID_IN_CSI0_D8") (class "Default")
      (node (ref "J1") (pin "58") (pinfunction "58_58") (pintype "passive"))
    )
    (net (code "132") (name "/VID_IN_CSI0_D9") (class "Default")
      (node (ref "J1") (pin "60") (pinfunction "60_60") (pintype "passive"))
    )
    (net (code "133") (name "/VID_IN_CSI0_D10") (class "Default")
      (node (ref "J1") (pin "62") (pinfunction "62_62") (pintype "passive"))
    )
    (net (code "134") (name "/VID_IN_CSI0_D11") (class "Default")
      (node (ref "J1") (pin "64") (pinfunction "64_64") (pintype "passive"))
    )
    (net (code "135") (name "/VID_IN_CSI0_D12") (class "Default")
      (node (ref "J1") (pin "61") (pinfunction "61_61") (pintype "passive"))
    )
    (net (code "136") (name "/VID_IN_CSI0_D13") (class "Default")
      (node (ref "J1") (pin "63") (pinfunction "63_63") (pintype "passive"))
    )
    (net (code "137") (name "/VID_IN_CSI0_D14") (class "Default")
      (node (ref "J1") (pin "65") (pinfunction "65_65") (pintype "passive"))
    )
    (net (code "138") (name "/VID_IN_CSI0_D15") (class "Default")
      (node (ref "J1") (pin "67") (pinfunction "67_67") (pintype "passive"))
    )
    (net (code "139") (name "/VID_IN_CSI0_D16") (class "Default")
      (node (ref "J1") (pin "68") (pinfunction "68_68") (pintype "passive"))
    )
    (net (code "140") (name "/VID_IN_CSI0_D17") (class "Default")
      (node (ref "J1") (pin "70") (pinfunction "70_70") (pintype "passive"))
    )
    (net (code "141") (name "/VID_IN_CSI0_D18") (class "Default")
      (node (ref "J1") (pin "72") (pinfunction "72_72") (pintype "passive"))
    )
    (net (code "142") (name "/VID_IN_CSI0_D19") (class "Default")
      (node (ref "J1") (pin "74") (pinfunction "74_74") (pintype "passive"))
    )
    (net (code "143") (name "/VID_IN_CSI0_DE") (class "Default")
      (node (ref "J1") (pin "75") (pinfunction "75_75") (pintype "passive"))
    )
    (net (code "144") (name "/VID_IN_CSI0_HS") (class "Default")
      (node (ref "J1") (pin "47") (pinfunction "47_47") (pintype "passive"))
    )
    (net (code "145") (name "/VID_IN_CSI0_INT") (class "Default")
      (node (ref "J1") (pin "73") (pinfunction "73_73") (pintype "passive"))
    )
    (net (code "146") (name "/VID_IN_CSI0_PIXCLK") (class "Default")
      (node (ref "J1") (pin "43") (pinfunction "43_43") (pintype "passive"))
    )
    (net (code "147") (name "/VID_IN_CSI0_RSTn") (class "Default")
      (node (ref "J1") (pin "71") (pinfunction "71_71") (pintype "passive"))
    )
    (net (code "148") (name "/VID_IN_CSI0_VS") (class "Default")
      (node (ref "J1") (pin "45") (pinfunction "45_45") (pintype "passive"))
    )
    (net (code "149") (name "GND") (class "Default")
      (node (ref "C1") (pin "2") (pinfunction "2_2") (pintype "passive"))
      (node (ref "C12") (pin "2") (pinfunction "2_2") (pintype "passive"))
      (node (ref "C13") (pin "2") (pinfunction "2_2") (pintype "passive"))
      (node (ref "C14") (pin "2") (pinfunction "2_2") (pintype "passive"))
      (node (ref "C15") (pin "2") (pinfunction "2_2") (pintype "passive"))
      (node (ref "C16") (pin "2") (pinfunction "2_2") (pintype "passive"))
      (node (ref "C2") (pin "2") (pinfunction "2_2") (pintype "passive"))
      (node (ref "C231") (pin "2") (pinfunction "2_2") (pintype "passive"))
      (node (ref "C232") (pin "2") (pinfunction "2_2") (pintype "passive"))
      (node (ref "C3") (pin "2") (pinfunction "2_2") (pintype "passive"))
      (node (ref "C4") (pin "2") (pinfunction "2_2") (pintype "passive"))
      (node (ref "C5") (pin "2") (pinfunction "2_2") (pintype "passive"))
      (node (ref "C6") (pin "2") (pinfunction "2_2") (pintype "passive"))
      (node (ref "C7") (pin "2") (pinfunction "2_2") (pintype "passive"))
      (node (ref "J1") (pin "11") (pinfunction "11_11") (pintype "passive"))
      (node (ref "J1") (pin "13") (pinfunction "13_13") (pintype "passive"))
      (node (ref "J1") (pin "15") (pinfunction "15_15") (pintype "passive"))
      (node (ref "J1") (pin "17") (pinfunction "17_17") (pintype "passive"))
      (node (ref "J1") (pin "19") (pinfunction "19_19") (pintype "passive"))
      (node (ref "J1") (pin "21") (pinfunction "21_21") (pintype "passive"))
      (node (ref "J1") (pin "23") (pinfunction "23_23") (pintype "passive"))
      (node (ref "J1") (pin "29") (pinfunction "29_29") (pintype "passive"))
      (node (ref "J1") (pin "30") (pinfunction "30_30") (pintype "passive"))
      (node (ref "J1") (pin "35") (pinfunction "35_35") (pintype "passive"))
      (node (ref "J1") (pin "36") (pinfunction "36_36") (pintype "passive"))
      (node (ref "J1") (pin "41") (pinfunction "41_41") (pintype "passive"))
      (node (ref "J1") (pin "49") (pinfunction "49_49") (pintype "passive"))
      (node (ref "J1") (pin "5") (pinfunction "5_5") (pintype "passive"))
      (node (ref "J1") (pin "56") (pinfunction "56_56") (pintype "passive"))
      (node (ref "J1") (pin "59") (pinfunction "59_59") (pintype "passive"))
      (node (ref "J1") (pin "66") (pinfunction "66_66") (pintype "passive"))
      (node (ref "J1") (pin "7") (pinfunction "7_7") (pintype "passive"))
      (node (ref "J1") (pin "83") (pinfunction "83_83") (pintype "passive"))
      (node (ref "J1") (pin "89") (pinfunction "89_89") (pintype "passive"))
      (node (ref "J1") (pin "9") (pinfunction "9_9") (pintype "passive"))
      (node (ref "J1") (pin "90") (pinfunction "90_90") (pintype "passive"))
      (node (ref "J1") (pin "95") (pinfunction "95_95") (pintype "passive"))
      (node (ref "J1") (pin "96") (pinfunction "96_96") (pintype "passive"))
      (node (ref "J2") (pin "11") (pinfunction "11_11") (pintype "passive"))
      (node (ref "J2") (pin "12") (pinfunction "12_12") (pintype "passive"))
      (node (ref "J2") (pin "21") (pinfunction "21_21") (pintype "passive"))
      (node (ref "J2") (pin "24") (pinfunction "24_24") (pintype "passive"))
      (node (ref "J2") (pin "31") (pinfunction "31_31") (pintype "passive"))
      (node (ref "J2") (pin "34") (pinfunction "34_34") (pintype "passive"))
      (node (ref "J2") (pin "40") (pinfunction "40_40") (pintype "passive"))
      (node (ref "J2") (pin "41") (pinfunction "41_41") (pintype "passive"))
      (node (ref "J2") (pin "46") (pinfunction "46_46") (pintype "passive"))
      (node (ref "J2") (pin "51") (pinfunction "51_51") (pintype "passive"))
      (node (ref "J2") (pin "56") (pinfunction "56_56") (pintype "passive"))
      (node (ref "J2") (pin "65") (pinfunction "65_65") (pintype "passive"))
      (node (ref "J2") (pin "66") (pinfunction "66_66") (pintype "passive"))
      (node (ref "J2") (pin "71") (pinfunction "71_71") (pintype "passive"))
      (node (ref "J2") (pin "77") (pinfunction "77_77") (pintype "passive"))
      (node (ref "J2") (pin "78") (pinfunction "78_78") (pintype "passive"))
      (node (ref "J2") (pin "83") (pinfunction "83_83") (pintype "passive"))
      (node (ref "J2") (pin "84") (pinfunction "84_84") (pintype "passive"))
      (node (ref "J2") (pin "89") (pinfunction "89_89") (pintype "passive"))
      (node (ref "J2") (pin "90") (pinfunction "90_90") (pintype "passive"))
      (node (ref "J2") (pin "95") (pinfunction "95_95") (pintype "passive"))
      (node (ref "J2") (pin "96") (pinfunction "96_96") (pintype "passive"))
      (node (ref "J3") (pin "11") (pinfunction "11_11") (pintype "passive"))
      (node (ref "J3") (pin "25") (pinfunction "25_25") (pintype "passive"))
      (node (ref "J3") (pin "28") (pinfunction "28_28") (pintype "passive"))
      (node (ref "J3") (pin "35") (pinfunction "35_35") (pintype "passive"))
      (node (ref "J3") (pin "38") (pinfunction "38_38") (pintype "passive"))
      (node (ref "J3") (pin "45") (pinfunction "45_45") (pintype "passive"))
      (node (ref "J3") (pin "5") (pinfunction "5_5") (pintype "passive"))
      (node (ref "J3") (pin "55") (pinfunction "55_55") (pintype "passive"))
      (node (ref "J3") (pin "68") (pinfunction "68_68") (pintype "passive"))
      (node (ref "J3") (pin "69") (pinfunction "69_69") (pintype "passive"))
      (node (ref "J3") (pin "79") (pinfunction "79_79") (pintype "passive"))
      (node (ref "J3") (pin "80") (pinfunction "80_80") (pintype "passive"))
      (node (ref "J3") (pin "91") (pinfunction "91_91") (pintype "passive"))
      (node (ref "J3") (pin "92") (pinfunction "92_92") (pintype "passive"))
    )
    (net (code "150") (name "unconnected-(J1-Pad25)") (class "Default")
      (node (ref "J1") (pin "25") (pinfunction "25_25") (pintype "passive+no_connect"))
    )
    (net (code "151") (name "unconnected-(J1-Pad26)") (class "Default")
      (node (ref "J1") (pin "26") (pinfunction "26_26") (pintype "passive+no_connect"))
    )
    (net (code "152") (name "unconnected-(J1-Pad27)") (class "Default")
      (node (ref "J1") (pin "27") (pinfunction "27_27") (pintype "passive+no_connect"))
    )
    (net (code "153") (name "unconnected-(J1-Pad28)") (class "Default")
      (node (ref "J1") (pin "28") (pinfunction "28_28") (pintype "passive+no_connect"))
    )
    (net (code "154") (name "unconnected-(J1-Pad31)") (class "Default")
      (node (ref "J1") (pin "31") (pinfunction "31_31") (pintype "passive+no_connect"))
    )
    (net (code "155") (name "unconnected-(J1-Pad32)") (class "Default")
      (node (ref "J1") (pin "32") (pinfunction "32_32") (pintype "passive+no_connect"))
    )
    (net (code "156") (name "unconnected-(J1-Pad33)") (class "Default")
      (node (ref "J1") (pin "33") (pinfunction "33_33") (pintype "passive+no_connect"))
    )
    (net (code "157") (name "unconnected-(J1-Pad34)") (class "Default")
      (node (ref "J1") (pin "34") (pinfunction "34_34") (pintype "passive+no_connect"))
    )
    (net (code "158") (name "unconnected-(J1-Pad37)") (class "Default")
      (node (ref "J1") (pin "37") (pinfunction "37_37") (pintype "passive+no_connect"))
    )
    (net (code "159") (name "unconnected-(J1-Pad39)") (class "Default")
      (node (ref "J1") (pin "39") (pinfunction "39_39") (pintype "passive+no_connect"))
    )
    (net (code "160") (name "unconnected-(J1-Pad91)") (class "Default")
      (node (ref "J1") (pin "91") (pinfunction "91_91") (pintype "passive+no_connect"))
    )
    (net (code "161") (name "unconnected-(J1-Pad93)") (class "Default")
      (node (ref "J1") (pin "93") (pinfunction "93_93") (pintype "passive+no_connect"))
    )
    (net (code "162") (name "unconnected-(J1-Pad97)") (class "Default")
      (node (ref "J1") (pin "97") (pinfunction "97_97") (pintype "passive+no_connect"))
    )
    (net (code "163") (name "unconnected-(J1-Pad98)") (class "Default")
      (node (ref "J1") (pin "98") (pinfunction "98_98") (pintype "passive+no_connect"))
    )
    (net (code "164") (name "unconnected-(J1-Pad99)") (class "Default")
      (node (ref "J1") (pin "99") (pinfunction "99_99") (pintype "passive+no_connect"))
    )
    (net (code "165") (name "unconnected-(J1-Pad100)") (class "Default")
      (node (ref "J1") (pin "100") (pinfunction "100_100") (pintype "passive+no_connect"))
    )
    (net (code "166") (name "unconnected-(J2-Pad1)") (class "Default")
      (node (ref "J2") (pin "1") (pinfunction "1_1") (pintype "passive+no_connect"))
    )
    (net (code "167") (name "unconnected-(J2-Pad20)") (class "Default")
      (node (ref "J2") (pin "20") (pinfunction "20_20") (pintype "passive+no_connect"))
    )
    (net (code "168") (name "unconnected-(J2-Pad91)") (class "Default")
      (node (ref "J2") (pin "91") (pinfunction "91_91") (pintype "passive+no_connect"))
    )
    (net (code "169") (name "unconnected-(J2-Pad93)") (class "Default")
      (node (ref "J2") (pin "93") (pinfunction "93_93") (pintype "passive+no_connect"))
    )
    (net (code "170") (name "unconnected-(J2-Pad97)") (class "Default")
      (node (ref "J2") (pin "97") (pinfunction "97_97") (pintype "passive+no_connect"))
    )
    (net (code "171") (name "unconnected-(J2-Pad99)") (class "Default")
      (node (ref "J2") (pin "99") (pinfunction "99_99") (pintype "passive+no_connect"))
    )
    (net (code "172") (name "unconnected-(J3-Pad13)") (class "Default")
      (node (ref "J3") (pin "13") (pinfunction "13_13") (pintype "passive+no_connect"))
    )
    (net (code "173") (name "unconnected-(J3-Pad15)") (class "Default")
      (node (ref "J3") (pin "15") (pinfunction "15_15") (pintype "passive+no_connect"))
    )
    (net (code "174") (name "unconnected-(J3-Pad17)") (class "Default")
      (node (ref "J3") (pin "17") (pinfunction "17_17") (pintype "passive+no_connect"))
    )
    (net (code "175") (name "unconnected-(J3-Pad18)") (class "Default")
      (node (ref "J3") (pin "18") (pinfunction "18_18") (pintype "passive+no_connect"))
    )
    (net (code "176") (name "unconnected-(J3-Pad21)") (class "Default")
      (node (ref "J3") (pin "21") (pinfunction "21_21") (pintype "passive+no_connect"))
    )
    (net (code "177") (name "unconnected-(J3-Pad23)") (class "Default")
      (node (ref "J3") (pin "23") (pinfunction "23_23") (pintype "passive+no_connect"))
    )
    (net (code "178") (name "unconnected-(J3-Pad24)") (class "Default")
      (node (ref "J3") (pin "24") (pinfunction "24_24") (pintype "passive+no_connect"))
    )
    (net (code "179") (name "unconnected-(J3-Pad26)") (class "Default")
      (node (ref "J3") (pin "26") (pinfunction "26_26") (pintype "passive+no_connect"))
    )
    (net (code "180") (name "unconnected-(J3-Pad27)") (class "Default")
      (node (ref "J3") (pin "27") (pinfunction "27_27") (pintype "passive+no_connect"))
    )
    (net (code "181") (name "unconnected-(J3-Pad29)") (class "Default")
      (node (ref "J3") (pin "29") (pinfunction "29_29") (pintype "passive+no_connect"))
    )
    (net (code "182") (name "unconnected-(J3-Pad30)") (class "Default")
      (node (ref "J3") (pin "30") (pinfunction "30_30") (pintype "passive+no_connect"))
    )
    (net (code "183") (name "unconnected-(J3-Pad31)") (class "Default")
      (node (ref "J3") (pin "31") (pinfunction "31_31") (pintype "passive+no_connect"))
    )
    (net (code "184") (name "unconnected-(J3-Pad32)") (class "Default")
      (node (ref "J3") (pin "32") (pinfunction "32_32") (pintype "passive+no_connect"))
    )
    (net (code "185") (name "unconnected-(J3-Pad33)") (class "Default")
      (node (ref "J3") (pin "33") (pinfunction "33_33") (pintype "passive+no_connect"))
    )
    (net (code "186") (name "unconnected-(J3-Pad34)") (class "Default")
      (node (ref "J3") (pin "34") (pinfunction "34_34") (pintype "passive+no_connect"))
    )
    (net (code "187") (name "unconnected-(J3-Pad36)") (class "Default")
      (node (ref "J3") (pin "36") (pinfunction "36_36") (pintype "passive+no_connect"))
    )
    (net (code "188") (name "unconnected-(J3-Pad37)") (class "Default")
      (node (ref "J3") (pin "37") (pinfunction "37_37") (pintype "passive+no_connect"))
    )
    (net (code "189") (name "unconnected-(J3-Pad39)") (class "Default")
      (node (ref "J3") (pin "39") (pinfunction "39_39") (pintype "passive+no_connect"))
    )
    (net (code "190") (name "unconnected-(J3-Pad40)") (class "Default")
      (node (ref "J3") (pin "40") (pinfunction "40_40") (pintype "passive+no_connect"))
    )
    (net (code "191") (name "unconnected-(J3-Pad41)") (class "Default")
      (node (ref "J3") (pin "41") (pinfunction "41_41") (pintype "passive+no_connect"))
    )
    (net (code "192") (name "unconnected-(J3-Pad42)") (class "Default")
      (node (ref "J3") (pin "42") (pinfunction "42_42") (pintype "passive+no_connect"))
    )
    (net (code "193") (name "unconnected-(J3-Pad43)") (class "Default")
      (node (ref "J3") (pin "43") (pinfunction "43_43") (pintype "passive+no_connect"))
    )
    (net (code "194") (name "unconnected-(J3-Pad44)") (class "Default")
      (node (ref "J3") (pin "44") (pinfunction "44_44") (pintype "passive+no_connect"))
    )
    (net (code "195") (name "unconnected-(J3-Pad46)") (class "Default")
      (node (ref "J3") (pin "46") (pinfunction "46_46") (pintype "passive+no_connect"))
    )
    (net (code "196") (name "unconnected-(J3-Pad47)") (class "Default")
      (node (ref "J3") (pin "47") (pinfunction "47_47") (pintype "passive+no_connect"))
    )
    (net (code "197") (name "unconnected-(J3-Pad49)") (class "Default")
      (node (ref "J3") (pin "49") (pinfunction "49_49") (pintype "passive+no_connect"))
    )
    (net (code "198") (name "unconnected-(J3-Pad51)") (class "Default")
      (node (ref "J3") (pin "51") (pinfunction "51_51") (pintype "passive+no_connect"))
    )
    (net (code "199") (name "unconnected-(J3-Pad53)") (class "Default")
      (node (ref "J3") (pin "53") (pinfunction "53_53") (pintype "passive+no_connect"))
    )
    (net (code "200") (name "unconnected-(J3-Pad57)") (class "Default")
      (node (ref "J3") (pin "57") (pinfunction "57_57") (pintype "passive+no_connect"))
    )
    (net (code "201") (name "unconnected-(J3-Pad59)") (class "Default")
      (node (ref "J3") (pin "59") (pinfunction "59_59") (pintype "passive+no_connect"))
    )
    (net (code "202") (name "unconnected-(J3-Pad61)") (class "Default")
      (node (ref "J3") (pin "61") (pinfunction "61_61") (pintype "passive+no_connect"))
    )
    (net (code "203") (name "unconnected-(J3-Pad63)") (class "Default")
      (node (ref "J3") (pin "63") (pinfunction "63_63") (pintype "passive+no_connect"))
    )
    (net (code "204") (name "unconnected-(J3-Pad65)") (class "Default")
      (node (ref "J3") (pin "65") (pinfunction "65_65") (pintype "passive+no_connect"))
    )
    (net (code "205") (name "unconnected-(J3-Pad67)") (class "Default")
      (node (ref "J3") (pin "67") (pinfunction "67_67") (pintype "passive+no_connect"))
    )
    (net (code "206") (name "unconnected-(J3-Pad81)") (class "Default")
      (node (ref "J3") (pin "81") (pinfunction "81_81") (pintype "passive+no_connect"))
    )
    (net (code "207") (name "unconnected-(J3-Pad82)") (class "Default")
      (node (ref "J3") (pin "82") (pinfunction "82_82") (pintype "passive+no_connect"))
    )
    (net (code "208") (name "unconnected-(J3-Pad83)") (class "Default")
      (node (ref "J3") (pin "83") (pinfunction "83_83") (pintype "passive+no_connect"))
    )
    (net (code "209") (name "unconnected-(J3-Pad84)") (class "Default")
      (node (ref "J3") (pin "84") (pinfunction "84_84") (pintype "passive+no_connect"))
    )
    (net (code "210") (name "unconnected-(J3-Pad85)") (class "Default")
      (node (ref "J3") (pin "85") (pinfunction "85_85") (pintype "passive+no_connect"))
    )
    (net (code "211") (name "unconnected-(J3-Pad86)") (class "Default")
      (node (ref "J3") (pin "86") (pinfunction "86_86") (pintype "passive+no_connect"))
    )
    (net (code "212") (name "unconnected-(J3-Pad87)") (class "Default")
      (node (ref "J3") (pin "87") (pinfunction "87_87") (pintype "passive+no_connect"))
    )
    (net (code "213") (name "unconnected-(J3-Pad88)") (class "Default")
      (node (ref "J3") (pin "88") (pinfunction "88_88") (pintype "passive+no_connect"))
    )
    (net (code "214") (name "unconnected-(J3-Pad89)") (class "Default")
      (node (ref "J3") (pin "89") (pinfunction "89_89") (pintype "passive+no_connect"))
    )
    (net (code "215") (name "unconnected-(J3-Pad90)") (class "Default")
      (node (ref "J3") (pin "90") (pinfunction "90_90") (pintype "passive+no_connect"))
    )
    (net (code "216") (name "unconnected-(J3-Pad93)") (class "Default")
      (node (ref "J3") (pin "93") (pinfunction "93_93") (pintype "passive+no_connect"))
    )
    (net (code "217") (name "unconnected-(J3-Pad94)") (class "Default")
      (node (ref "J3") (pin "94") (pinfunction "94_94") (pintype "passive+no_connect"))
    )
    (net (code "218") (name "unconnected-(J3-Pad95)") (class "Default")
      (node (ref "J3") (pin "95") (pinfunction "95_95") (pintype "passive+no_connect"))
    )
    (net (code "219") (name "unconnected-(J3-Pad96)") (class "Default")
      (node (ref "J3") (pin "96") (pinfunction "96_96") (pintype "passive+no_connect"))
    )
    (net (code "220") (name "unconnected-(J3-Pad97)") (class "Default")
      (node (ref "J3") (pin "97") (pinfunction "97_97") (pintype "passive+no_connect"))
    )
    (net (code "221") (name "unconnected-(J3-Pad98)") (class "Default")
      (node (ref "J3") (pin "98") (pinfunction "98_98") (pintype "passive+no_connect"))
    )
    (net (code "222") (name "unconnected-(J3-Pad99)") (class "Default")
      (node (ref "J3") (pin "99") (pinfunction "99_99") (pintype "passive+no_connect"))
    )
    (net (code "223") (name "unconnected-(J3-Pad100)") (class "Default")
      (node (ref "J3") (pin "100") (pinfunction "100_100") (pintype "passive+no_connect"))
    )
  )
)
